# powerSMALL.net
KiCad netlist of a schematic drawn in EAGLE
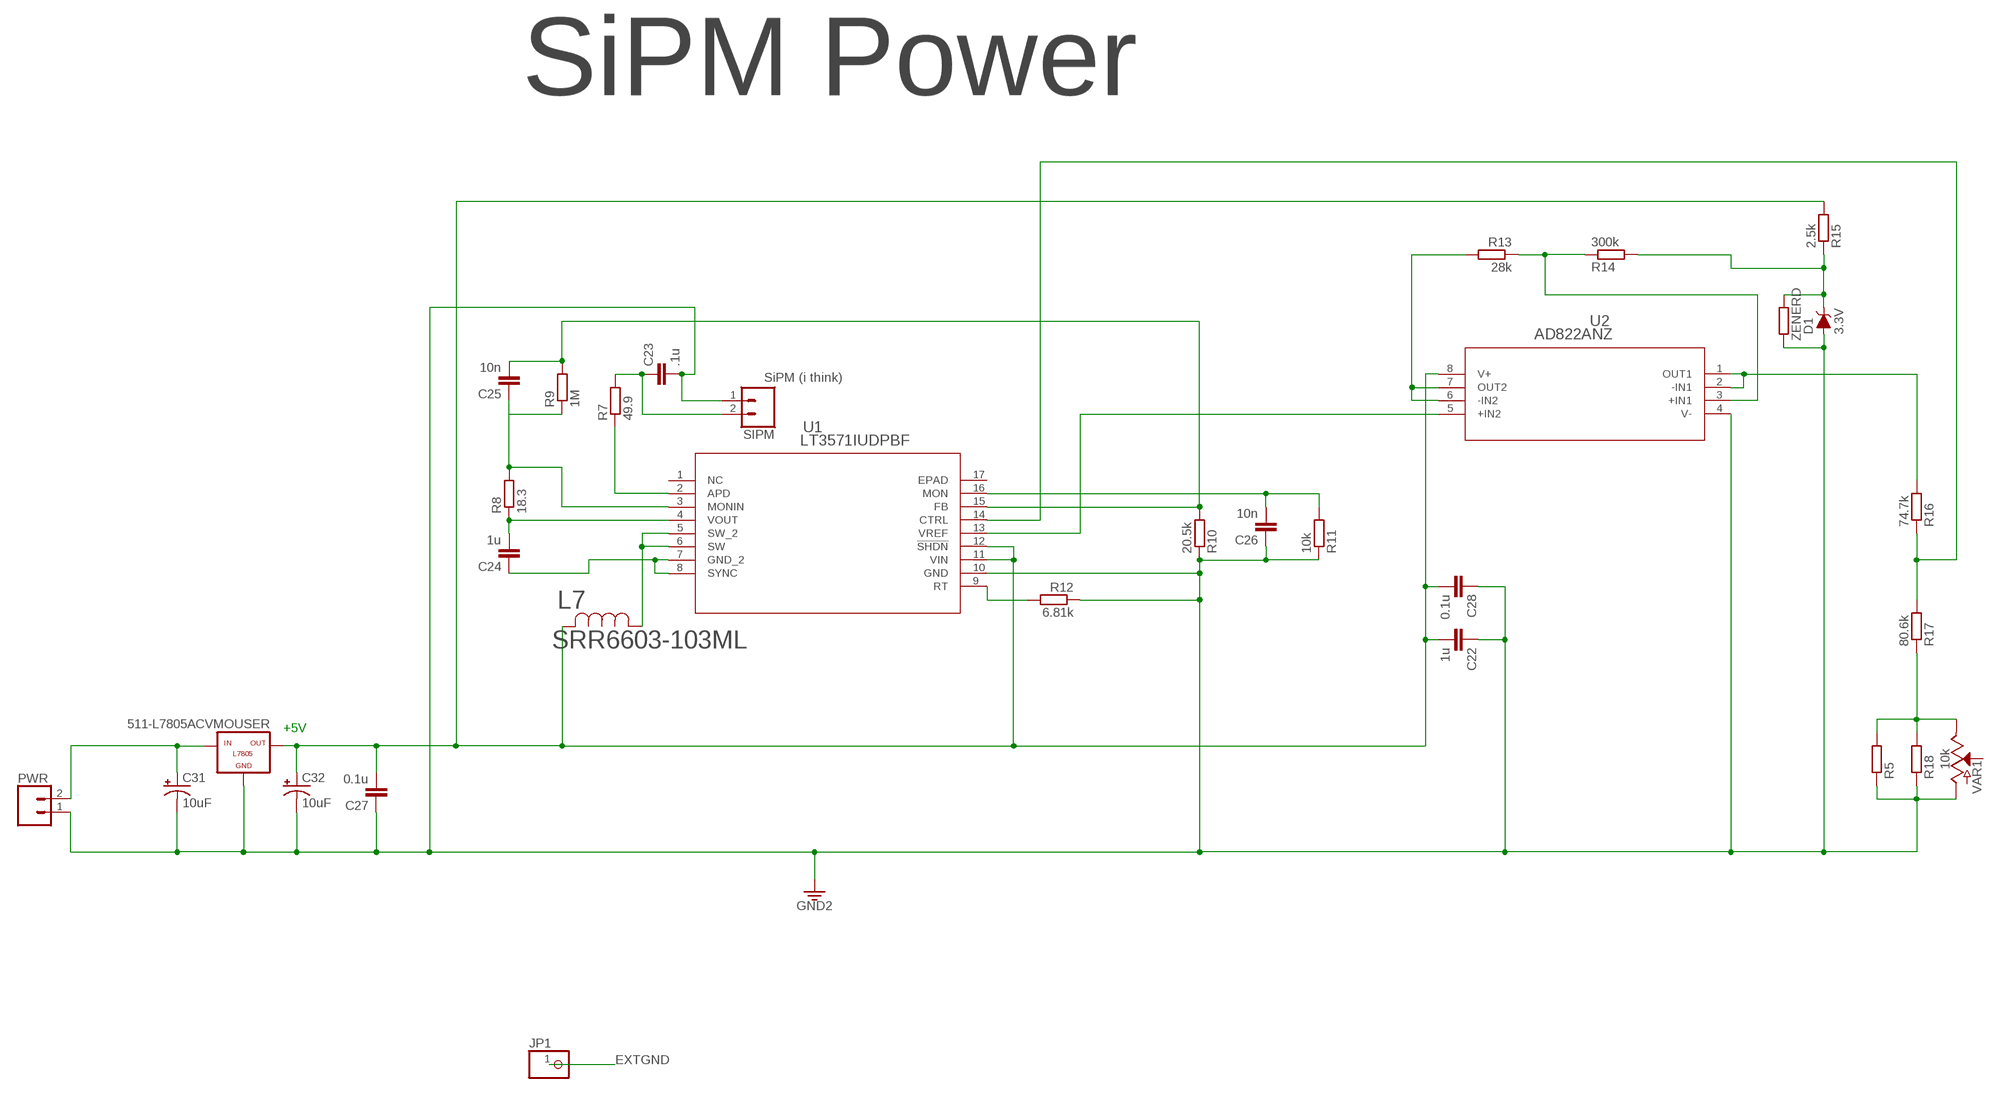
[diagram p0: schematic, sheet 1, part 1 of 2]
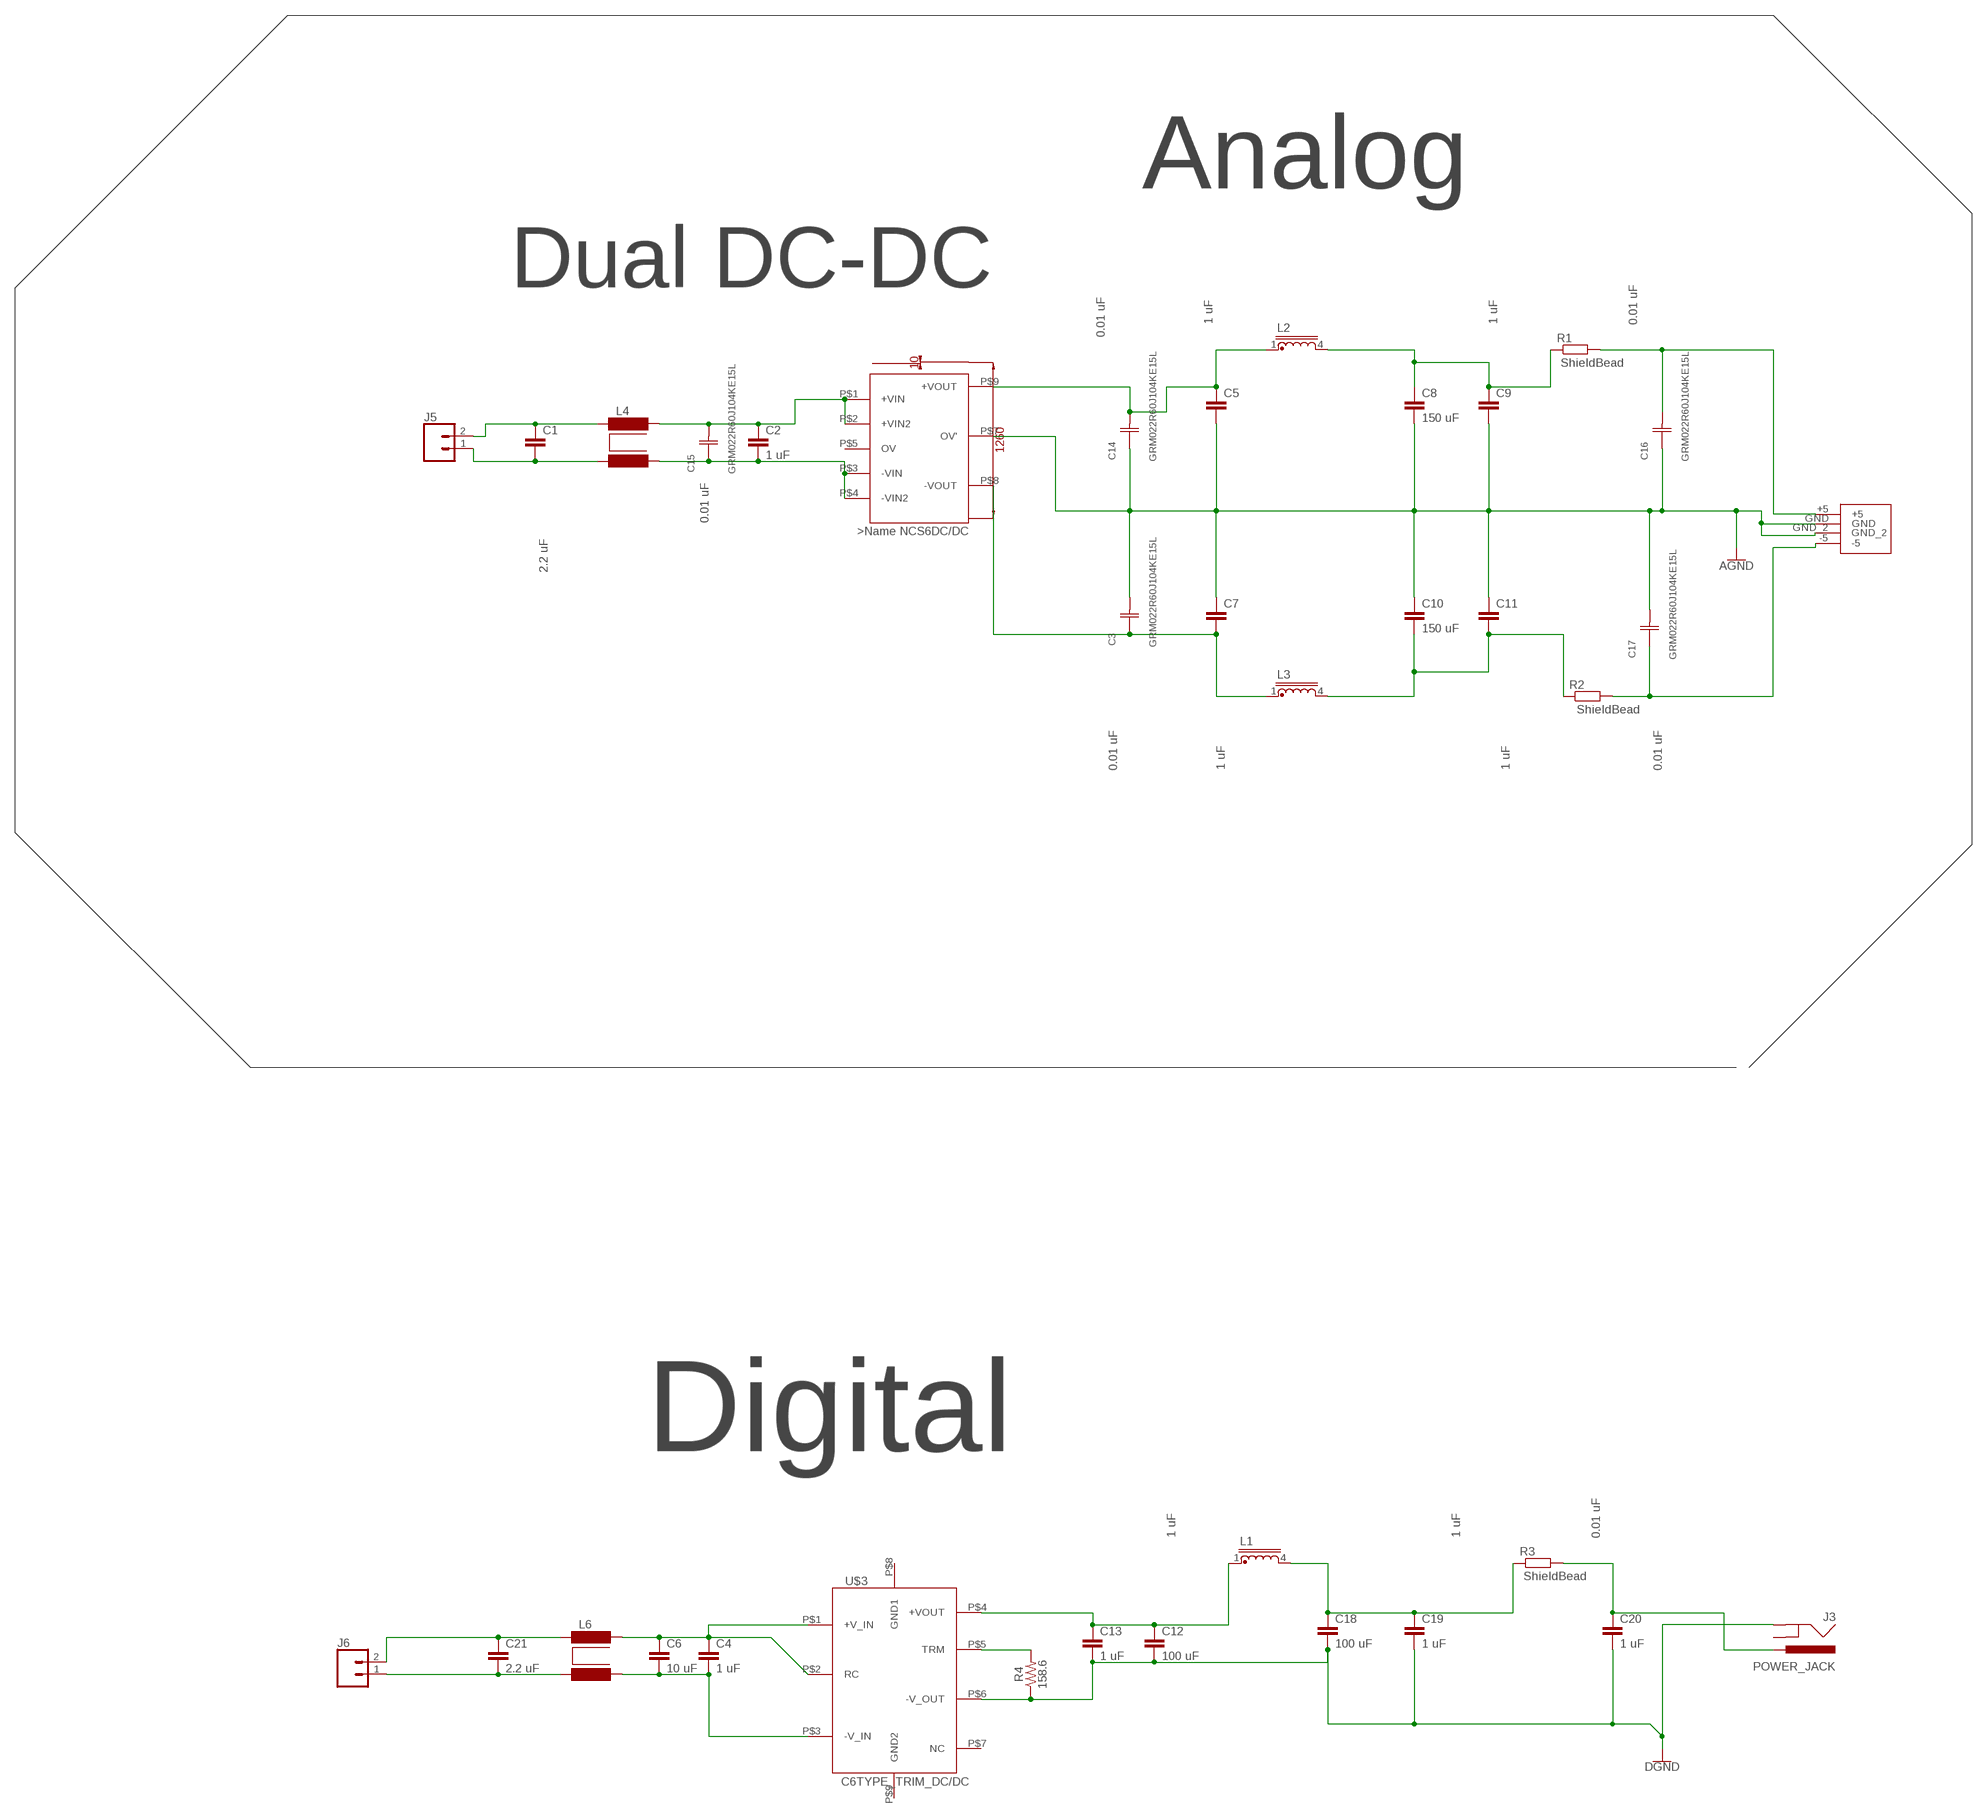
[diagram p1: schematic, sheet 1, part 2 of 2]

(export (version "E")
  (design (tool "Eeschema 10.0.6"))
  (components
    (comp (ref "511-L7805ACVMOUSER")
      (value "-L7805")
      (footprint "eagle-import:L7805")
      (libsource (lib "eagle-import") (part "-L7805"))
    )
    (comp (ref "C1")
      (value "C2.5/2")
      (footprint "eagle-import:C2.5-2")
      (libsource (lib "eagle-import") (part "C2.5/2"))
    )
    (comp (ref "C2")
      (value "1 uF")
      (footprint "eagle-import:CAP-PTH-10MM")
      (libsource (lib "eagle-import") (part "10NF-PTH-10MM-10000V-1-%"))
    )
    (comp (ref "C3")
      (value "GRM022R60J104KE15L")
      (footprint "eagle-import:CAP_GRM02L_P42XP22")
      (libsource (lib "eagle-import") (part "GRM022R60J104KE15L"))
    )
    (comp (ref "C4")
      (value "1 uF")
      (footprint "eagle-import:CAP-PTH-10MM")
      (libsource (lib "eagle-import") (part "10NF-PTH-10MM-10000V-1-%"))
    )
    (comp (ref "C5")
      (value "C2.5/2")
      (footprint "eagle-import:C2.5-2")
      (libsource (lib "eagle-import") (part "C2.5/2"))
    )
    (comp (ref "C6")
      (value "10 uF")
      (footprint "eagle-import:CAP-PTH-10MM")
      (libsource (lib "eagle-import") (part "10NF-PTH-10MM-10000V-1-%"))
    )
    (comp (ref "C7")
      (value "C2.5/2")
      (footprint "eagle-import:C2.5-2")
      (libsource (lib "eagle-import") (part "C2.5/2"))
    )
    (comp (ref "C8")
      (value "150 uF")
      (footprint "eagle-import:CAP-PTH-10MM")
      (libsource (lib "eagle-import") (part "10NF-PTH-10MM-10000V-1-%"))
    )
    (comp (ref "C9")
      (value "C2.5/2")
      (footprint "eagle-import:C2.5-2")
      (libsource (lib "eagle-import") (part "C2.5/2"))
    )
    (comp (ref "C10")
      (value "150 uF")
      (footprint "eagle-import:CAP-PTH-10MM")
      (libsource (lib "eagle-import") (part "10NF-PTH-10MM-10000V-1-%"))
    )
    (comp (ref "C11")
      (value "C2.5/2")
      (footprint "eagle-import:C2.5-2")
      (libsource (lib "eagle-import") (part "C2.5/2"))
    )
    (comp (ref "C12")
      (value "100 uF")
      (footprint "eagle-import:CAP-PTH-10MM")
      (libsource (lib "eagle-import") (part "10NF-PTH-10MM-10000V-1-%"))
    )
    (comp (ref "C13")
      (value "1 uF")
      (footprint "eagle-import:CAP-PTH-10MM")
      (libsource (lib "eagle-import") (part "10NF-PTH-10MM-10000V-1-%"))
    )
    (comp (ref "C14")
      (value "GRM022R60J104KE15L")
      (footprint "eagle-import:CAP_GRM02L_P42XP22")
      (libsource (lib "eagle-import") (part "GRM022R60J104KE15L"))
    )
    (comp (ref "C15")
      (value "GRM022R60J104KE15L")
      (footprint "eagle-import:CAP_GRM02L_P42XP22")
      (libsource (lib "eagle-import") (part "GRM022R60J104KE15L"))
    )
    (comp (ref "C16")
      (value "GRM022R60J104KE15L")
      (footprint "eagle-import:CAP_GRM02L_P42XP22")
      (libsource (lib "eagle-import") (part "GRM022R60J104KE15L"))
    )
    (comp (ref "C17")
      (value "GRM022R60J104KE15L")
      (footprint "eagle-import:CAP_GRM02L_P42XP22")
      (libsource (lib "eagle-import") (part "GRM022R60J104KE15L"))
    )
    (comp (ref "C18")
      (value "100 uF")
      (footprint "eagle-import:CAP-PTH-10MM")
      (libsource (lib "eagle-import") (part "10NF-PTH-10MM-10000V-1-%"))
    )
    (comp (ref "C19")
      (value "1 uF")
      (footprint "eagle-import:CAP-PTH-10MM")
      (libsource (lib "eagle-import") (part "10NF-PTH-10MM-10000V-1-%"))
    )
    (comp (ref "C20")
      (value "1 uF")
      (footprint "eagle-import:CAP-PTH-10MM")
      (libsource (lib "eagle-import") (part "10NF-PTH-10MM-10000V-1-%"))
    )
    (comp (ref "C21")
      (value "2.2 uF")
      (footprint "eagle-import:CAP-PTH-10MM")
      (libsource (lib "eagle-import") (part "10NF-PTH-10MM-10000V-1-%"))
    )
    (comp (ref "C22")
      (value "1u")
      (footprint "eagle-import:C2.5-2")
      (libsource (lib "eagle-import") (part "C2.5/2"))
    )
    (comp (ref "C23")
      (value ".1u")
      (footprint "eagle-import:C2.5-2")
      (libsource (lib "eagle-import") (part "C2.5/2"))
    )
    (comp (ref "C24")
      (value "1u")
      (footprint "eagle-import:C2.5-2")
      (libsource (lib "eagle-import") (part "C2.5/2"))
    )
    (comp (ref "C25")
      (value "10n")
      (footprint "eagle-import:C2.5-2")
      (libsource (lib "eagle-import") (part "C2.5/2"))
    )
    (comp (ref "C26")
      (value "10n")
      (footprint "eagle-import:C2.5-2")
      (libsource (lib "eagle-import") (part "C2.5/2"))
    )
    (comp (ref "C27")
      (value "0.1u")
      (footprint "eagle-import:C2.5-2")
      (libsource (lib "eagle-import") (part "C2.5/2"))
    )
    (comp (ref "C28")
      (value "0.1u")
      (footprint "eagle-import:C2.5-2")
      (libsource (lib "eagle-import") (part "C2.5/2"))
    )
    (comp (ref "C31")
      (value "10uF")
      (footprint "eagle-import:0603-POLAR")
      (libsource (lib "eagle-import") (part "10UF-POLAR-0603-6.3V-20%(TANT)"))
    )
    (comp (ref "C32")
      (value "10uF")
      (footprint "eagle-import:0603-POLAR")
      (libsource (lib "eagle-import") (part "10UF-POLAR-0603-6.3V-20%(TANT)"))
    )
    (comp (ref "D1")
      (value "3.3V")
      (footprint "eagle-import:SOD-323")
      (libsource (lib "eagle-import") (part "DIODE-ZENER-MM3Z3V3T1G"))
    )
    (comp (ref "J3")
      (value "POWER_JACK")
      (footprint "eagle-import:POWER_JACK_PTH")
      (libsource (lib "eagle-import") (part "POWER_JACK"))
    )
    (comp (ref "J5")
      (value "CONN_02PTH4")
      (footprint "eagle-import:1X02_XTRA_BIG")
      (libsource (lib "eagle-import") (part "CONN_02PTH4"))
    )
    (comp (ref "J6")
      (value "CONN_02PTH4")
      (footprint "eagle-import:1X02_XTRA_BIG")
      (libsource (lib "eagle-import") (part "CONN_02PTH4"))
    )
    (comp (ref "JP1")
      (value "PINHD-1X1")
      (footprint "eagle-import:1X01")
      (libsource (lib "eagle-import") (part "PINHD-1X1"))
    )
    (comp (ref "L1")
      (value "U15-CHOKE")
      (footprint "eagle-import:U15CHOKE")
      (libsource (lib "eagle-import") (part "U15-CHOKE"))
    )
    (comp (ref "L2")
      (value "U15-CHOKE")
      (footprint "eagle-import:U15CHOKE")
      (libsource (lib "eagle-import") (part "U15-CHOKE"))
    )
    (comp (ref "L3")
      (value "U15-CHOKE")
      (footprint "eagle-import:U15CHOKE")
      (libsource (lib "eagle-import") (part "U15-CHOKE"))
    )
    (comp (ref "L4")
      (value "SMR6-I")
      (footprint "eagle-import:SM-R6")
      (libsource (lib "eagle-import") (part "SMR6-I"))
    )
    (comp (ref "L6")
      (value "SMR6-I")
      (footprint "eagle-import:SM-R6")
      (libsource (lib "eagle-import") (part "SMR6-I"))
    )
    (comp (ref "L7")
      (value "SRR6603-103ML")
      (footprint "eagle-import:IND_BOURNS_SRR6603")
      (fields (field (name "MANUFACTURER_PART_NUMBER") "SRR6603103ML"))
      (libsource (lib "eagle-import") (part "SRR6603-103ML"))
    )
    (comp (ref "PWR")
      (value "CONN_02PTH4")
      (footprint "eagle-import:1X02_XTRA_BIG")
      (libsource (lib "eagle-import") (part "CONN_02PTH4"))
    )
    (comp (ref "R1")
      (value "R0207/10")
      (footprint "eagle-import:0207_10")
      (libsource (lib "eagle-import") (part "R0207/10"))
    )
    (comp (ref "R2")
      (value "R0207/10")
      (footprint "eagle-import:0207_10")
      (libsource (lib "eagle-import") (part "R0207/10"))
    )
    (comp (ref "R3")
      (value "R0207/10")
      (footprint "eagle-import:0207_10")
      (libsource (lib "eagle-import") (part "R0207/10"))
    )
    (comp (ref "R4")
      (value "158.6")
      (footprint "eagle-import:AXIAL-0.3")
      (libsource (lib "eagle-import") (part "10MOHM-HORIZ-1/4W-5%"))
    )
    (comp (ref "R5")
      (value "R0207/10")
      (footprint "eagle-import:0207_10")
      (libsource (lib "eagle-import") (part "R0207/10"))
    )
    (comp (ref "R7")
      (value "49.9")
      (footprint "eagle-import:0207_10")
      (libsource (lib "eagle-import") (part "R0207/10"))
    )
    (comp (ref "R8")
      (value "18.3")
      (footprint "eagle-import:0207_10")
      (libsource (lib "eagle-import") (part "R0207/10"))
    )
    (comp (ref "R9")
      (value "1M")
      (footprint "eagle-import:0207_10")
      (libsource (lib "eagle-import") (part "R0207/10"))
    )
    (comp (ref "R10")
      (value "20.5k")
      (footprint "eagle-import:0207_10")
      (libsource (lib "eagle-import") (part "R0207/10"))
    )
    (comp (ref "R11")
      (value "10k")
      (footprint "eagle-import:0207_10")
      (libsource (lib "eagle-import") (part "R0207/10"))
    )
    (comp (ref "R12")
      (value "6.81k")
      (footprint "eagle-import:0207_10")
      (libsource (lib "eagle-import") (part "R0207/10"))
    )
    (comp (ref "R13")
      (value "28k")
      (footprint "eagle-import:0207_10")
      (libsource (lib "eagle-import") (part "R0207/10"))
    )
    (comp (ref "R14")
      (value "300k")
      (footprint "eagle-import:0207_10")
      (libsource (lib "eagle-import") (part "R0207/10"))
    )
    (comp (ref "R15")
      (value "2.5k")
      (footprint "eagle-import:0207_10")
      (libsource (lib "eagle-import") (part "R0207/10"))
    )
    (comp (ref "R16")
      (value "74.7k")
      (footprint "eagle-import:0207_10")
      (libsource (lib "eagle-import") (part "R0207/10"))
    )
    (comp (ref "R17")
      (value "80.6k")
      (footprint "eagle-import:0207_10")
      (libsource (lib "eagle-import") (part "R0207/10"))
    )
    (comp (ref "R18")
      (value "R0207/10")
      (footprint "eagle-import:0207_10")
      (libsource (lib "eagle-import") (part "R0207/10"))
    )
    (comp (ref "SIPM")
      (value "CONN_02PTH4")
      (footprint "eagle-import:1X02_XTRA_BIG")
      (libsource (lib "eagle-import") (part "CONN_02PTH4"))
    )
    (comp (ref "U$1")
      (value "NCS6D1205")
      (footprint "eagle-import:NCS6D1205C")
      (libsource (lib "eagle-import") (part "NCS6D1205"))
    )
    (comp (ref "U$3")
      (value "C6TYPE_TRIM_DC/DC")
      (footprint "eagle-import:CONV_DC_DC_6W_SNGL_C6TYPE")
      (libsource (lib "eagle-import") (part "C6TYPE_TRIM_DC/DC"))
    )
    (comp (ref "U$4")
      (value "WM403_NDPOWER_JACK")
      (footprint "eagle-import:WM4302-ND")
      (libsource (lib "eagle-import") (part "WM403_NDPOWER_JACK"))
    )
    (comp (ref "U1")
      (value "LT3571IUDPBF")
      (footprint "eagle-import:QFN-16_UD")
      (fields (field (name "MANUFACTURER_PART_NUMBER") "LT3571IUD#PBF"))
      (libsource (lib "eagle-import") (part "LT3571IUDPBF"))
    )
    (comp (ref "U2")
      (value "AD822ANZ")
      (footprint "eagle-import:N_8")
      (libsource (lib "eagle-import") (part "AD822ANZ"))
    )
    (comp (ref "VAR1")
      (value "10k")
      (footprint "eagle-import:POT-PTH-ALPS")
      (libsource (lib "eagle-import") (part "POTENTIOMETER-PTH-9MM-1/20W-20%"))
    )
    (comp (ref "ZENERD")
      (value "R0207/10")
      (footprint "eagle-import:0207_10")
      (libsource (lib "eagle-import") (part "R0207/10"))
    )
  )
  (nets
    (net (code "1") (name "/EXTGND") (class "Default")
      (node (ref "JP1") (pin "1") (pinfunction "1_1") (pintype "passive"))
    )
    (net (code "2") (name "AGND") (class "Default")
      (node (ref "C10") (pin "1") (pinfunction "1_1") (pintype "passive"))
      (node (ref "C11") (pin "1") (pinfunction "1_1") (pintype "passive"))
      (node (ref "C14") (pin "1") (pinfunction "11_1") (pintype "passive"))
      (node (ref "C16") (pin "1") (pinfunction "11_1") (pintype "passive"))
      (node (ref "C17") (pin "2") (pinfunction "22_2") (pintype "passive"))
      (node (ref "C3") (pin "2") (pinfunction "22_2") (pintype "passive"))
      (node (ref "C5") (pin "2") (pinfunction "2_2") (pintype "passive"))
      (node (ref "C7") (pin "1") (pinfunction "1_1") (pintype "passive"))
      (node (ref "C8") (pin "2") (pinfunction "2_2") (pintype "passive"))
      (node (ref "C9") (pin "2") (pinfunction "2_2") (pintype "passive"))
      (node (ref "U$1") (pin "P$7") (pinfunction "OV'_P$7") (pintype "bidirectional"))
      (node (ref "U$4") (pin "GND") (pinfunction "GND_GND") (pintype "bidirectional"))
      (node (ref "U$4") (pin "GND_2") (pinfunction "GND_2_GND_2") (pintype "bidirectional"))
    )
    (net (code "3") (name "DGND") (class "Default")
      (node (ref "C12") (pin "2") (pinfunction "2_2") (pintype "passive"))
      (node (ref "C13") (pin "2") (pinfunction "2_2") (pintype "passive"))
      (node (ref "C18") (pin "2") (pinfunction "2_2") (pintype "passive"))
      (node (ref "C19") (pin "2") (pinfunction "2_2") (pintype "passive"))
      (node (ref "C20") (pin "2") (pinfunction "2_2") (pintype "passive"))
      (node (ref "J3") (pin "GND") (pinfunction "GND_GND") (pintype "bidirectional"))
      (node (ref "R4") (pin "P$1") (pinfunction "1_P$1") (pintype "passive"))
      (node (ref "U$3") (pin "P$6") (pinfunction "-V_OUT_P$6") (pintype "bidirectional"))
    )
    (net (code "4") (name "GND2") (class "Default")
      (node (ref "511-L7805ACVMOUSER") (pin "GND") (pinfunction "GND_GND") (pintype "input"))
      (node (ref "C22") (pin "1") (pinfunction "1_1") (pintype "passive"))
      (node (ref "C23") (pin "2") (pinfunction "2_2") (pintype "passive"))
      (node (ref "C26") (pin "1") (pinfunction "1_1") (pintype "passive"))
      (node (ref "C27") (pin "1") (pinfunction "1_1") (pintype "passive"))
      (node (ref "C28") (pin "1") (pinfunction "1_1") (pintype "passive"))
      (node (ref "C31") (pin "-") (pinfunction "-_-") (pintype "passive"))
      (node (ref "C32") (pin "-") (pinfunction "-_-") (pintype "passive"))
      (node (ref "D1") (pin "A") (pinfunction "A_A") (pintype "passive"))
      (node (ref "PWR") (pin "1") (pinfunction "1_1") (pintype "passive"))
      (node (ref "R10") (pin "1") (pinfunction "1_1") (pintype "passive"))
      (node (ref "R11") (pin "1") (pinfunction "1_1") (pintype "passive"))
      (node (ref "R12") (pin "1") (pinfunction "1_1") (pintype "passive"))
      (node (ref "R18") (pin "1") (pinfunction "1_1") (pintype "passive"))
      (node (ref "R5") (pin "1") (pinfunction "1_1") (pintype "passive"))
      (node (ref "SIPM") (pin "1") (pinfunction "1_1") (pintype "passive"))
      (node (ref "U1") (pin "10") (pinfunction "GND_10") (pintype "power_in"))
      (node (ref "U2") (pin "4") (pinfunction "V-_4") (pintype "power_in"))
      (node (ref "VAR1") (pin "P$3") (pinfunction "A_P$3") (pintype "passive"))
      (node (ref "ZENERD") (pin "1") (pinfunction "1_1") (pintype "passive"))
    )
    (net (code "5") (name "Net-(511-L7805ACVMOUSER-PadIN)") (class "Default")
      (node (ref "511-L7805ACVMOUSER") (pin "IN") (pinfunction "IN_IN") (pintype "input"))
      (node (ref "C31") (pin "+") (pinfunction "+_+") (pintype "passive"))
      (node (ref "PWR") (pin "2") (pinfunction "2_2") (pintype "passive"))
    )
    (net (code "6") (name "Net-(C1-Pad1)") (class "Default")
      (node (ref "C1") (pin "1") (pinfunction "1_1") (pintype "passive"))
      (node (ref "J5") (pin "2") (pinfunction "2_2") (pintype "passive"))
      (node (ref "L4") (pin "1") (pinfunction "1_1") (pintype "passive"))
    )
    (net (code "7") (name "Net-(C1-Pad2)") (class "Default")
      (node (ref "C1") (pin "2") (pinfunction "2_2") (pintype "passive"))
      (node (ref "J5") (pin "1") (pinfunction "1_1") (pintype "passive"))
      (node (ref "L4") (pin "4") (pinfunction "4_4") (pintype "passive"))
    )
    (net (code "8") (name "Net-(C3-11)") (class "Default")
      (node (ref "C3") (pin "1") (pinfunction "11_1") (pintype "passive"))
      (node (ref "C7") (pin "2") (pinfunction "2_2") (pintype "passive"))
      (node (ref "L3") (pin "1") (pinfunction "1_1") (pintype "passive"))
      (node (ref "U$1") (pin "P$8") (pinfunction "-VOUT_P$8") (pintype "bidirectional"))
    )
    (net (code "9") (name "Net-(C8-Pad1)") (class "Default")
      (node (ref "C8") (pin "1") (pinfunction "1_1") (pintype "passive"))
      (node (ref "C9") (pin "1") (pinfunction "1_1") (pintype "passive"))
      (node (ref "L2") (pin "4") (pinfunction "4_4") (pintype "passive"))
      (node (ref "R1") (pin "1") (pinfunction "1_1") (pintype "passive"))
    )
    (net (code "10") (name "Net-(C10-Pad2)") (class "Default")
      (node (ref "C10") (pin "2") (pinfunction "2_2") (pintype "passive"))
      (node (ref "C11") (pin "2") (pinfunction "2_2") (pintype "passive"))
      (node (ref "L3") (pin "4") (pinfunction "4_4") (pintype "passive"))
      (node (ref "R2") (pin "1") (pinfunction "1_1") (pintype "passive"))
    )
    (net (code "11") (name "Net-(C14-22)") (class "Default")
      (node (ref "C14") (pin "2") (pinfunction "22_2") (pintype "passive"))
      (node (ref "C5") (pin "1") (pinfunction "1_1") (pintype "passive"))
      (node (ref "L2") (pin "1") (pinfunction "1_1") (pintype "passive"))
      (node (ref "U$1") (pin "P$9") (pinfunction "+VOUT_P$9") (pintype "bidirectional"))
    )
    (net (code "12") (name "Net-(C15-11)") (class "Default")
      (node (ref "C15") (pin "1") (pinfunction "11_1") (pintype "passive"))
      (node (ref "C2") (pin "2") (pinfunction "2_2") (pintype "passive"))
      (node (ref "L4") (pin "5") (pinfunction "5_5") (pintype "passive"))
      (node (ref "U$1") (pin "P$3") (pinfunction "-VIN_P$3") (pintype "bidirectional"))
      (node (ref "U$1") (pin "P$4") (pinfunction "-VIN2_P$4") (pintype "bidirectional"))
    )
    (net (code "13") (name "Net-(C15-22)") (class "Default")
      (node (ref "C15") (pin "2") (pinfunction "22_2") (pintype "passive"))
      (node (ref "C2") (pin "1") (pinfunction "1_1") (pintype "passive"))
      (node (ref "L4") (pin "8") (pinfunction "8_8") (pintype "passive"))
      (node (ref "U$1") (pin "P$1") (pinfunction "+VIN_P$1") (pintype "power_in"))
      (node (ref "U$1") (pin "P$2") (pinfunction "+VIN2_P$2") (pintype "power_in"))
    )
    (net (code "14") (name "Net-(C16-22)") (class "Default")
      (node (ref "C16") (pin "2") (pinfunction "22_2") (pintype "passive"))
      (node (ref "R1") (pin "2") (pinfunction "2_2") (pintype "passive"))
      (node (ref "U$4") (pin "+5") (pinfunction "+5_+5") (pintype "bidirectional"))
    )
    (net (code "15") (name "Net-(C17-11)") (class "Default")
      (node (ref "C17") (pin "1") (pinfunction "11_1") (pintype "passive"))
      (node (ref "R2") (pin "2") (pinfunction "2_2") (pintype "passive"))
      (node (ref "U$4") (pin "-5") (pinfunction "-5_-5") (pintype "bidirectional"))
    )
    (net (code "16") (name "Net-(C18-Pad1)") (class "Default")
      (node (ref "C18") (pin "1") (pinfunction "1_1") (pintype "passive"))
      (node (ref "C19") (pin "1") (pinfunction "1_1") (pintype "passive"))
      (node (ref "L1") (pin "4") (pinfunction "4_4") (pintype "passive"))
      (node (ref "R3") (pin "1") (pinfunction "1_1") (pintype "passive"))
    )
    (net (code "17") (name "Net-(C20-Pad1)") (class "Default")
      (node (ref "C20") (pin "1") (pinfunction "1_1") (pintype "passive"))
      (node (ref "J3") (pin "PWR") (pinfunction "PWR_PWR") (pintype "bidirectional"))
      (node (ref "R3") (pin "2") (pinfunction "2_2") (pintype "passive"))
    )
    (net (code "18") (name "Net-(C21-Pad1)") (class "Default")
      (node (ref "C21") (pin "1") (pinfunction "1_1") (pintype "passive"))
      (node (ref "J6") (pin "2") (pinfunction "2_2") (pintype "passive"))
      (node (ref "L6") (pin "1") (pinfunction "1_1") (pintype "passive"))
    )
    (net (code "19") (name "Net-(C21-Pad2)") (class "Default")
      (node (ref "C21") (pin "2") (pinfunction "2_2") (pintype "passive"))
      (node (ref "J6") (pin "1") (pinfunction "1_1") (pintype "passive"))
      (node (ref "L6") (pin "4") (pinfunction "4_4") (pintype "passive"))
    )
    (net (code "20") (name "Net-(C23-Pad1)") (class "Default")
      (node (ref "C23") (pin "1") (pinfunction "1_1") (pintype "passive"))
      (node (ref "R7") (pin "2") (pinfunction "2_2") (pintype "passive"))
      (node (ref "SIPM") (pin "2") (pinfunction "2_2") (pintype "passive"))
    )
    (net (code "21") (name "Net-(D1-PadC)") (class "Default")
      (node (ref "D1") (pin "C") (pinfunction "C_C") (pintype "passive"))
      (node (ref "R14") (pin "2") (pinfunction "2_2") (pintype "passive"))
      (node (ref "R15") (pin "1") (pinfunction "1_1") (pintype "passive"))
      (node (ref "ZENERD") (pin "2") (pinfunction "2_2") (pintype "passive"))
    )
    (net (code "22") (name "Net-(R4-2)") (class "Default")
      (node (ref "R4") (pin "P$2") (pinfunction "2_P$2") (pintype "passive"))
      (node (ref "U$3") (pin "P$5") (pinfunction "TRM_P$5") (pintype "bidirectional"))
    )
    (net (code "23") (name "Net-(U$3-+VOUT)") (class "Default")
      (node (ref "C12") (pin "1") (pinfunction "1_1") (pintype "passive"))
      (node (ref "C13") (pin "1") (pinfunction "1_1") (pintype "passive"))
      (node (ref "L1") (pin "1") (pinfunction "1_1") (pintype "passive"))
      (node (ref "U$3") (pin "P$4") (pinfunction "+VOUT_P$4") (pintype "bidirectional"))
    )
    (net (code "24") (name "Net-(U$3-+V_IN)") (class "Default")
      (node (ref "C4") (pin "1") (pinfunction "1_1") (pintype "passive"))
      (node (ref "C6") (pin "1") (pinfunction "1_1") (pintype "passive"))
      (node (ref "L6") (pin "8") (pinfunction "8_8") (pintype "passive"))
      (node (ref "U$3") (pin "P$1") (pinfunction "+V_IN_P$1") (pintype "bidirectional"))
      (node (ref "U$3") (pin "P$2") (pinfunction "RC_P$2") (pintype "bidirectional"))
    )
    (net (code "25") (name "Net-(U$3--V_IN)") (class "Default")
      (node (ref "C4") (pin "2") (pinfunction "2_2") (pintype "passive"))
      (node (ref "C6") (pin "2") (pinfunction "2_2") (pintype "passive"))
      (node (ref "L6") (pin "5") (pinfunction "5_5") (pintype "passive"))
      (node (ref "U$3") (pin "P$3") (pinfunction "-V_IN_P$3") (pintype "bidirectional"))
    )
    (net (code "26") (name "Net-(U1-APD)") (class "Default")
      (node (ref "R7") (pin "1") (pinfunction "1_1") (pintype "passive"))
      (node (ref "U1") (pin "2") (pinfunction "APD_2") (pintype "passive"))
    )
    (net (code "27") (name "Net-(U1-CTRL)") (class "Default")
      (node (ref "R16") (pin "1") (pinfunction "1_1") (pintype "passive"))
      (node (ref "R17") (pin "2") (pinfunction "2_2") (pintype "passive"))
      (node (ref "U1") (pin "14") (pinfunction "CTRL_14") (pintype "output"))
    )
    (net (code "28") (name "Net-(U1-FB)") (class "Default")
      (node (ref "C25") (pin "2") (pinfunction "2_2") (pintype "passive"))
      (node (ref "R10") (pin "2") (pinfunction "2_2") (pintype "passive"))
      (node (ref "R9") (pin "2") (pinfunction "2_2") (pintype "passive"))
      (node (ref "U1") (pin "15") (pinfunction "FB_15") (pintype "output"))
    )
    (net (code "29") (name "Net-(U1-GND_2)") (class "Default")
      (node (ref "C24") (pin "1") (pinfunction "1_1") (pintype "passive"))
      (node (ref "U1") (pin "7") (pinfunction "GND_2_7") (pintype "power_in"))
      (node (ref "U1") (pin "8") (pinfunction "SYNC_8") (pintype "passive"))
    )
    (net (code "30") (name "Net-(U1-MON)") (class "Default")
      (node (ref "C26") (pin "2") (pinfunction "2_2") (pintype "passive"))
      (node (ref "R11") (pin "2") (pinfunction "2_2") (pintype "passive"))
      (node (ref "U1") (pin "16") (pinfunction "MON_16") (pintype "output"))
    )
    (net (code "31") (name "Net-(U1-MONIN)") (class "Default")
      (node (ref "C25") (pin "1") (pinfunction "1_1") (pintype "passive"))
      (node (ref "R8") (pin "2") (pinfunction "2_2") (pintype "passive"))
      (node (ref "R9") (pin "1") (pinfunction "1_1") (pintype "passive"))
      (node (ref "U1") (pin "3") (pinfunction "MONIN_3") (pintype "input"))
    )
    (net (code "32") (name "Net-(U1-RT)") (class "Default")
      (node (ref "R12") (pin "2") (pinfunction "2_2") (pintype "passive"))
      (node (ref "U1") (pin "9") (pinfunction "RT_9") (pintype "passive"))
    )
    (net (code "33") (name "Net-(U1-SW)") (class "Default")
      (node (ref "L7") (pin "1") (pinfunction "1_1") (pintype "passive"))
      (node (ref "U1") (pin "5") (pinfunction "SW_2_5") (pintype "passive"))
      (node (ref "U1") (pin "6") (pinfunction "SW_6") (pintype "passive"))
    )
    (net (code "34") (name "Net-(U1-VIN)") (class "Default")
      (node (ref "511-L7805ACVMOUSER") (pin "OUT") (pinfunction "OUT_OUT") (pintype "passive"))
      (node (ref "C22") (pin "2") (pinfunction "2_2") (pintype "passive"))
      (node (ref "C27") (pin "2") (pinfunction "2_2") (pintype "passive"))
      (node (ref "C28") (pin "2") (pinfunction "2_2") (pintype "passive"))
      (node (ref "C32") (pin "+") (pinfunction "+_+") (pintype "passive"))
      (node (ref "L7") (pin "2") (pinfunction "2_2") (pintype "passive"))
      (node (ref "R15") (pin "2") (pinfunction "2_2") (pintype "passive"))
      (node (ref "U1") (pin "11") (pinfunction "VIN_11") (pintype "input"))
      (node (ref "U1") (pin "12") (pinfunction "~{SHDN}_12") (pintype "passive"))
      (node (ref "U2") (pin "8") (pinfunction "V+_8") (pintype "power_in"))
    )
    (net (code "35") (name "Net-(U1-VOUT)") (class "Default")
      (node (ref "C24") (pin "2") (pinfunction "2_2") (pintype "passive"))
      (node (ref "R8") (pin "1") (pinfunction "1_1") (pintype "passive"))
      (node (ref "U1") (pin "4") (pinfunction "VOUT_4") (pintype "output"))
    )
    (net (code "36") (name "Net-(U1-VREF)") (class "Default")
      (node (ref "U1") (pin "13") (pinfunction "VREF_13") (pintype "output"))
      (node (ref "U2") (pin "5") (pinfunction "+IN2_5") (pintype "passive"))
    )
    (net (code "37") (name "Net-(U2-+IN1)") (class "Default")
      (node (ref "R13") (pin "1") (pinfunction "1_1") (pintype "passive"))
      (node (ref "R14") (pin "1") (pinfunction "1_1") (pintype "passive"))
      (node (ref "U2") (pin "3") (pinfunction "+IN1_3") (pintype "passive"))
    )
    (net (code "38") (name "Net-(U2--IN1)") (class "Default")
      (node (ref "R16") (pin "2") (pinfunction "2_2") (pintype "passive"))
      (node (ref "U2") (pin "1") (pinfunction "OUT1_1") (pintype "passive"))
      (node (ref "U2") (pin "2") (pinfunction "-IN1_2") (pintype "passive"))
    )
    (net (code "39") (name "Net-(U2--IN2)") (class "Default")
      (node (ref "R13") (pin "2") (pinfunction "2_2") (pintype "passive"))
      (node (ref "U2") (pin "6") (pinfunction "-IN2_6") (pintype "passive"))
      (node (ref "U2") (pin "7") (pinfunction "OUT2_7") (pintype "passive"))
    )
    (net (code "40") (name "Net-(VAR1-E)") (class "Default")
      (node (ref "R17") (pin "1") (pinfunction "1_1") (pintype "passive"))
      (node (ref "R18") (pin "2") (pinfunction "2_2") (pintype "passive"))
      (node (ref "R5") (pin "2") (pinfunction "2_2") (pintype "passive"))
      (node (ref "VAR1") (pin "P$1") (pinfunction "E_P$1") (pintype "passive"))
    )
    (net (code "41") (name "unconnected-(J3-PadGNDBREAK)") (class "Default")
      (node (ref "J3") (pin "GNDBREAK") (pinfunction "GNDBREAK_GNDBREAK") (pintype "bidirectional"))
    )
    (net (code "42") (name "unconnected-(U$1-OV-PadP$5)") (class "Default")
      (node (ref "U$1") (pin "P$5") (pinfunction "OV_P$5") (pintype "bidirectional"))
    )
    (net (code "43") (name "unconnected-(U$3-GND1-PadP$8)") (class "Default")
      (node (ref "U$3") (pin "P$8") (pinfunction "GND1_P$8") (pintype "bidirectional"))
    )
    (net (code "44") (name "unconnected-(U$3-GND2-PadP$9)") (class "Default")
      (node (ref "U$3") (pin "P$9") (pinfunction "GND2_P$9") (pintype "bidirectional"))
    )
    (net (code "45") (name "unconnected-(U$3-NC-PadP$7)") (class "Default")
      (node (ref "U$3") (pin "P$7") (pinfunction "NC_P$7") (pintype "bidirectional"))
    )
    (net (code "46") (name "unconnected-(U1-EPAD-Pad17)") (class "Default")
      (node (ref "U1") (pin "17") (pinfunction "EPAD_17") (pintype "passive"))
    )
    (net (code "47") (name "unconnected-(U1-NC-Pad1)") (class "Default")
      (node (ref "U1") (pin "1") (pinfunction "NC_1") (pintype "no_connect"))
    )
    (net (code "48") (name "unconnected-(VAR1-S-PadP$2)") (class "Default")
      (node (ref "VAR1") (pin "P$2") (pinfunction "S_P$2") (pintype "passive"))
    )
  )
)
